# remout_pwr.net
KiCad netlist of a schematic drawn in Altium Designer
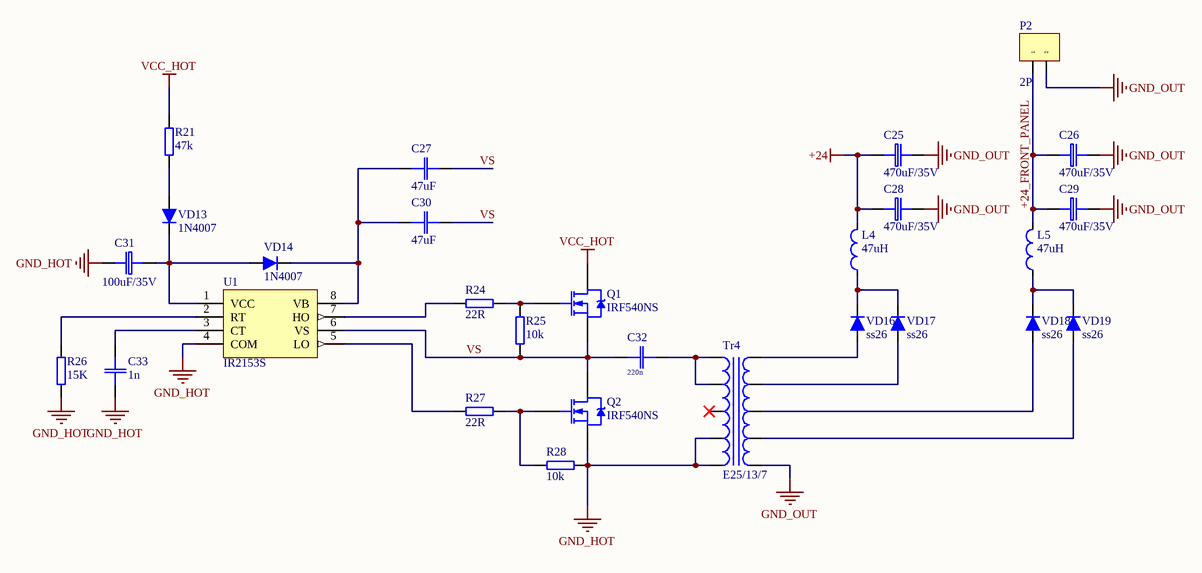
[diagram p0: remout_pwr.SchDoc]

(export (version "E")
  (design (tool "Eeschema 10.0.6"))
  (components
    (comp (ref "C25")
      (value "470uF/35V")
      (footprint "CAP: D6.3C2.5H11")
      (libsource (lib "PASSIVE") (part "C_EL"))
    )
    (comp (ref "C26")
      (value "470uF/35V")
      (footprint "CAP: D6.3C2.5H11")
      (libsource (lib "PASSIVE") (part "C_EL"))
    )
    (comp (ref "C27") (value "47uF") (footprint "CAP: 1210") (libsource (lib "PASSIVE") (part "C_SMD")))
    (comp (ref "C28")
      (value "470uF/35V")
      (footprint "CAP: D6.3C2.5H11")
      (libsource (lib "PASSIVE") (part "C_EL"))
    )
    (comp (ref "C29")
      (value "470uF/35V")
      (footprint "CAP: D6.3C2.5H11")
      (libsource (lib "PASSIVE") (part "C_EL"))
    )
    (comp (ref "C30") (value "47uF") (footprint "CAP: 1210") (libsource (lib "PASSIVE") (part "C_SMD")))
    (comp (ref "C31") (value "100uF/35V") (footprint "CAP: D6.3C2.5H11") (libsource (lib "") (part "C_EL_1")))
    (comp (ref "C32")
      (value "220n")
      (footprint "MKP 13x5 h11 R10")
      (description "MKS4 68n 400V")
      (libsource (lib "Cap") (part "MKS4 68n 400V"))
    )
    (comp (ref "C33") (value "1n") (footprint "CAP: 0805") (libsource (lib "PASSIVE") (part "C_SMD")))
    (comp (ref "L4") (value "47uH") (footprint "IND: SRP1265A") (libsource (lib "PASSIVE") (part "L_SMD")))
    (comp (ref "L5") (value "47uH") (footprint "IND: SRP1265A") (libsource (lib "PASSIVE") (part "L_SMD")))
    (comp (ref "P2") (value "2P") (footprint "CON: 2P V 3.5mm") (libsource (lib "CONNECTOR") (part "2P")))
    (comp (ref "Q1")
      (value "IRF540NS")
      (footprint "D2PAK_N")
      (description "HEXFET Power MOSFET")
      (fields (field (name "PUBLISHER") "Altium Limited"))
      (libsource (lib "IR Discrete MOSFET - Power") (part "IRF540NS"))
    )
    (comp (ref "Q2")
      (value "IRF540NS")
      (footprint "D2PAK_N")
      (description "HEXFET Power MOSFET")
      (fields (field (name "PUBLISHER") "Altium Limited"))
      (libsource (lib "IR Discrete MOSFET - Power") (part "IRF540NS"))
    )
    (comp (ref "R21") (value "47k") (footprint "RES: 2W H") (libsource (lib "PASSIVE") (part "R_DIP")))
    (comp (ref "R24") (value "22R") (footprint "RES: 0805") (libsource (lib "PASSIVE") (part "R_SMD")))
    (comp (ref "R25") (value "10k") (footprint "RES: 0805") (libsource (lib "PASSIVE") (part "R_SMD")))
    (comp (ref "R26") (value "15K") (footprint "RES: 0805") (libsource (lib "PASSIVE") (part "R_SMD")))
    (comp (ref "R27") (value "22R") (footprint "RES: 0805") (libsource (lib "PASSIVE") (part "R_SMD")))
    (comp (ref "R28") (value "10k") (footprint "RES: 0805") (libsource (lib "PASSIVE") (part "R_SMD")))
    (comp (ref "Tr4")
      (value "E25/13/7")
      (footprint "TRANS: E25/13/7")
      (libsource (lib "TRANS") (part "E25/13/7"))
    )
    (comp (ref "U1")
      (value "IR2153S")
      (footprint "SO-8_N")
      (description "Self-Oscillating Half-Bridge Driver")
      (fields (field (name "PUBLISHER") "Altium Limited"))
      (libsource (lib "IR Interface Bridge Driver") (part "IR2153S"))
    )
    (comp (ref "VD13")
      (value "1N4007")
      (footprint "DIODE: SMA")
      (libsource (lib "DIODES") (part "DIODE_SMD"))
    )
    (comp (ref "VD14")
      (value "1N4007")
      (footprint "DIODE: SMA")
      (libsource (lib "DIODES") (part "DIODE_SMD"))
    )
    (comp (ref "VD16") (value "ss26") (footprint "DIODE: SMA") (libsource (lib "DIODES") (part "DIODE_SMD")))
    (comp (ref "VD17") (value "ss26") (footprint "DIODE: SMA") (libsource (lib "DIODES") (part "DIODE_SMD")))
    (comp (ref "VD18") (value "ss26") (footprint "DIODE: SMA") (libsource (lib "DIODES") (part "DIODE_SMD")))
    (comp (ref "VD19") (value "ss26") (footprint "DIODE: SMA") (libsource (lib "DIODES") (part "DIODE_SMD")))
  )
  (nets
    (net (code "1") (name "+24") (class "Default")
      (node (ref "C25") (pin "1") (pinfunction "+_1") (pintype "passive"))
      (node (ref "C28") (pin "1") (pinfunction "+_1") (pintype "passive"))
      (node (ref "L4") (pin "2") (pinfunction "2_2") (pintype "passive"))
    )
    (net (code "2") (name "/+24_FRONT_PANEL") (class "Default")
      (node (ref "C26") (pin "1") (pinfunction "+_1") (pintype "passive"))
      (node (ref "C29") (pin "1") (pinfunction "+_1") (pintype "passive"))
      (node (ref "L5") (pin "2") (pinfunction "2_2") (pintype "passive"))
      (node (ref "P2") (pin "1") (pinfunction "1_1") (pintype "passive"))
    )
    (net (code "3") (name "/VS") (class "Default")
      (node (ref "C27") (pin "1") (pinfunction "1_1") (pintype "passive"))
      (node (ref "C30") (pin "1") (pinfunction "1_1") (pintype "passive"))
      (node (ref "C32") (pin "1") (pinfunction "1_1") (pintype "passive"))
      (node (ref "Q1") (pin "3") (pinfunction "S_3") (pintype "passive"))
      (node (ref "Q2") (pin "2") (pinfunction "D_2") (pintype "passive"))
      (node (ref "R25") (pin "1") (pinfunction "1_1") (pintype "passive"))
      (node (ref "U1") (pin "6") (pinfunction "VS_6") (pintype "power_in"))
    )
    (net (code "4") (name "GND_HOT") (class "Default")
      (node (ref "C31") (pin "2") (pinfunction "-_2") (pintype "passive"))
      (node (ref "C33") (pin "1") (pinfunction "1_1") (pintype "passive"))
      (node (ref "Q2") (pin "3") (pinfunction "S_3") (pintype "passive"))
      (node (ref "R26") (pin "2") (pinfunction "2_2") (pintype "passive"))
      (node (ref "R28") (pin "1") (pinfunction "1_1") (pintype "passive"))
      (node (ref "Tr4") (pin "4") (pinfunction "4_4") (pintype "passive"))
      (node (ref "Tr4") (pin "5") (pinfunction "5_5") (pintype "passive"))
      (node (ref "U1") (pin "4") (pinfunction "COM_4") (pintype "power_in"))
    )
    (net (code "5") (name "GND_OUT") (class "Default")
      (node (ref "C25") (pin "2") (pinfunction "-_2") (pintype "passive"))
      (node (ref "C26") (pin "2") (pinfunction "-_2") (pintype "passive"))
      (node (ref "C28") (pin "2") (pinfunction "-_2") (pintype "passive"))
      (node (ref "C29") (pin "2") (pinfunction "-_2") (pintype "passive"))
      (node (ref "P2") (pin "2") (pinfunction "2_2") (pintype "passive"))
      (node (ref "Tr4") (pin "6") (pinfunction "6_6") (pintype "passive"))
    )
    (net (code "6") (name "Net-(C31-+)") (class "Default")
      (node (ref "C31") (pin "1") (pinfunction "+_1") (pintype "passive"))
      (node (ref "U1") (pin "1") (pinfunction "VCC_1") (pintype "power_in"))
      (node (ref "VD13") (pin "2") (pinfunction "C_2") (pintype "passive"))
      (node (ref "VD14") (pin "1") (pinfunction "A_1") (pintype "passive"))
    )
    (net (code "7") (name "Net-(C32-Pad2)") (class "Default")
      (node (ref "C32") (pin "2") (pinfunction "2_2") (pintype "passive"))
      (node (ref "Tr4") (pin "1") (pinfunction "1_1") (pintype "passive"))
      (node (ref "Tr4") (pin "2") (pinfunction "2_2") (pintype "passive"))
    )
    (net (code "8") (name "Net-(Q1-G)") (class "Default")
      (node (ref "Q1") (pin "1") (pinfunction "G_1") (pintype "passive"))
      (node (ref "R24") (pin "2") (pinfunction "2_2") (pintype "passive"))
      (node (ref "R25") (pin "2") (pinfunction "2_2") (pintype "passive"))
    )
    (net (code "9") (name "Net-(Q2-G)") (class "Default")
      (node (ref "Q2") (pin "1") (pinfunction "G_1") (pintype "passive"))
      (node (ref "R27") (pin "2") (pinfunction "2_2") (pintype "passive"))
      (node (ref "R28") (pin "2") (pinfunction "2_2") (pintype "passive"))
    )
    (net (code "10") (name "Net-(U1-CT)") (class "Default")
      (node (ref "C33") (pin "2") (pinfunction "2_2") (pintype "passive"))
      (node (ref "U1") (pin "3") (pinfunction "CT_3") (pintype "passive"))
    )
    (net (code "11") (name "Net-(U1-HO)") (class "Default")
      (node (ref "R24") (pin "1") (pinfunction "1_1") (pintype "passive"))
      (node (ref "U1") (pin "7") (pinfunction "HO_7") (pintype "output"))
    )
    (net (code "12") (name "Net-(U1-LO)") (class "Default")
      (node (ref "R27") (pin "1") (pinfunction "1_1") (pintype "passive"))
      (node (ref "U1") (pin "5") (pinfunction "LO_5") (pintype "output"))
    )
    (net (code "13") (name "Net-(U1-RT)") (class "Default")
      (node (ref "R26") (pin "1") (pinfunction "1_1") (pintype "passive"))
      (node (ref "U1") (pin "2") (pinfunction "RT_2") (pintype "passive"))
    )
    (net (code "14") (name "Net-(U1-VB)") (class "Default")
      (node (ref "C27") (pin "2") (pinfunction "2_2") (pintype "passive"))
      (node (ref "C30") (pin "2") (pinfunction "2_2") (pintype "passive"))
      (node (ref "U1") (pin "8") (pinfunction "VB_8") (pintype "power_in"))
      (node (ref "VD14") (pin "2") (pinfunction "C_2") (pintype "passive"))
    )
    (net (code "15") (name "Net-(VD13-A)") (class "Default")
      (node (ref "R21") (pin "2") (pinfunction "2_2") (pintype "passive"))
      (node (ref "VD13") (pin "1") (pinfunction "A_1") (pintype "passive"))
    )
    (net (code "16") (name "Net-(VD16-A)") (class "Default")
      (node (ref "Tr4") (pin "10") (pinfunction "10_10") (pintype "passive"))
      (node (ref "VD16") (pin "1") (pinfunction "A_1") (pintype "passive"))
    )
    (net (code "17") (name "Net-(VD16-C)") (class "Default")
      (node (ref "L4") (pin "1") (pinfunction "1_1") (pintype "passive"))
      (node (ref "VD16") (pin "2") (pinfunction "C_2") (pintype "passive"))
      (node (ref "VD17") (pin "2") (pinfunction "C_2") (pintype "passive"))
    )
    (net (code "18") (name "Net-(VD17-A)") (class "Default")
      (node (ref "Tr4") (pin "9") (pinfunction "9_9") (pintype "passive"))
      (node (ref "VD17") (pin "1") (pinfunction "A_1") (pintype "passive"))
    )
    (net (code "19") (name "Net-(VD18-A)") (class "Default")
      (node (ref "Tr4") (pin "8") (pinfunction "8_8") (pintype "passive"))
      (node (ref "VD18") (pin "1") (pinfunction "A_1") (pintype "passive"))
    )
    (net (code "20") (name "Net-(VD18-C)") (class "Default")
      (node (ref "L5") (pin "1") (pinfunction "1_1") (pintype "passive"))
      (node (ref "VD18") (pin "2") (pinfunction "C_2") (pintype "passive"))
      (node (ref "VD19") (pin "2") (pinfunction "C_2") (pintype "passive"))
    )
    (net (code "21") (name "Net-(VD19-A)") (class "Default")
      (node (ref "Tr4") (pin "7") (pinfunction "7_7") (pintype "passive"))
      (node (ref "VD19") (pin "1") (pinfunction "A_1") (pintype "passive"))
    )
    (net (code "22") (name "VCC_HOT") (class "Default")
      (node (ref "Q1") (pin "2") (pinfunction "D_2") (pintype "passive"))
      (node (ref "R21") (pin "1") (pinfunction "1_1") (pintype "passive"))
    )
    (net (code "23") (name "unconnected-(Tr4-Pad3)") (class "Default")
      (node (ref "Tr4") (pin "3") (pinfunction "3_3") (pintype "passive+no_connect"))
    )
  )
)
